# sbr.net
KiCad netlist of a schematic drawn in EAGLE
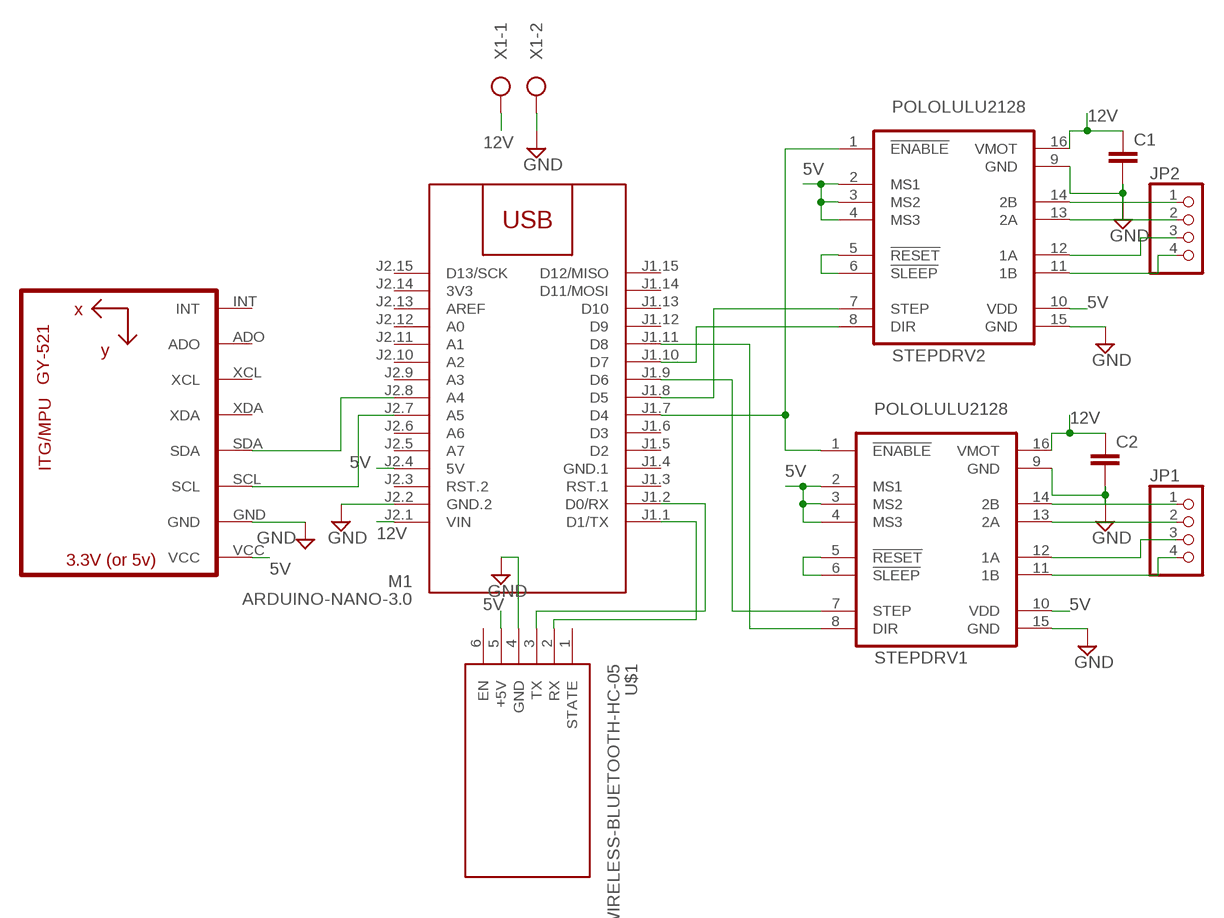
[diagram p0: schematic, sheet 1]

(export (version "E")
  (design (tool "Eeschema 10.0.6"))
  (components
    (comp (ref "C1")
      (value "C-EU025-024X044")
      (footprint "eagle-import:C025-024X044")
      (libsource (lib "eagle-import") (part "C-EU025-024X044"))
    )
    (comp (ref "C2")
      (value "C-EU025-024X044")
      (footprint "eagle-import:C025-024X044")
      (libsource (lib "eagle-import") (part "C-EU025-024X044"))
    )
    (comp (ref "JP1")
      (value "PINHD-1X4")
      (footprint "eagle-import:1X04")
      (libsource (lib "eagle-import") (part "PINHD-1X4"))
    )
    (comp (ref "JP2")
      (value "PINHD-1X4")
      (footprint "eagle-import:1X04")
      (libsource (lib "eagle-import") (part "PINHD-1X4"))
    )
    (comp (ref "M1")
      (value "ARDUINO-NANO-3.0")
      (footprint "eagle-import:ARDUINO-NANO-3.0")
      (libsource (lib "eagle-import") (part "ARDUINO-NANO-3.0"))
    )
    (comp (ref "STEPDRV1")
      (value "POLOLULU2128")
      (footprint "eagle-import:POLOLULU2128")
      (libsource (lib "eagle-import") (part "POLOLULU2128"))
    )
    (comp (ref "STEPDRV2")
      (value "POLOLULU2128")
      (footprint "eagle-import:POLOLULU2128")
      (libsource (lib "eagle-import") (part "POLOLULU2128"))
    )
    (comp (ref "U$1")
      (value "WIRELESS-BLUETOOTH-HC-05")
      (footprint "eagle-import:WIRELESS-BLUETOOTH-HC-05")
      (libsource (lib "eagle-import") (part "WIRELESS-BLUETOOTH-HC-05"))
    )
    (comp (ref "U1")
      (value "GY-521MPU6050")
      (footprint "eagle-import:GY-521")
      (libsource (lib "eagle-import") (part "GY-521MPU6050"))
    )
    (comp (ref "X1")
      (value "W237-102")
      (footprint "eagle-import:W237-102")
      (fields (field (name "MPN") "237-102"))
      (libsource (lib "eagle-import") (part "W237-102"))
    )
  )
  (nets
    (net (code "1") (name "/3V3") (class "Default")
      (node (ref "M1") (pin "J2.14") (pinfunction "3V3_J2.14") (pintype "power_in"))
    )
    (net (code "2") (name "/5V") (class "Default")
      (node (ref "M1") (pin "J2.4") (pinfunction "5V_J2.4") (pintype "power_in"))
      (node (ref "STEPDRV1") (pin "10") (pinfunction "VDD_10") (pintype "power_in"))
      (node (ref "STEPDRV1") (pin "2") (pinfunction "MS1_2") (pintype "input"))
      (node (ref "STEPDRV1") (pin "3") (pinfunction "MS2_3") (pintype "input"))
      (node (ref "STEPDRV1") (pin "4") (pinfunction "MS3_4") (pintype "input"))
      (node (ref "STEPDRV2") (pin "10") (pinfunction "VDD_10") (pintype "power_in"))
      (node (ref "STEPDRV2") (pin "2") (pinfunction "MS1_2") (pintype "input"))
      (node (ref "STEPDRV2") (pin "3") (pinfunction "MS2_3") (pintype "input"))
      (node (ref "STEPDRV2") (pin "4") (pinfunction "MS3_4") (pintype "input"))
      (node (ref "U$1") (pin "5") (pinfunction "+5V_5") (pintype "power_in"))
      (node (ref "U1") (pin "VCC") (pinfunction "VCC_VCC") (pintype "bidirectional"))
    )
    (net (code "3") (name "/12V") (class "Default")
      (node (ref "C1") (pin "1") (pinfunction "1_1") (pintype "passive"))
      (node (ref "C2") (pin "1") (pinfunction "1_1") (pintype "passive"))
      (node (ref "M1") (pin "J2.1") (pinfunction "VIN_J2.1") (pintype "power_in"))
      (node (ref "STEPDRV1") (pin "16") (pinfunction "VMOT_16") (pintype "power_in"))
      (node (ref "STEPDRV2") (pin "16") (pinfunction "VMOT_16") (pintype "power_in"))
      (node (ref "X1") (pin "1") (pinfunction "KL_1") (pintype "passive"))
    )
    (net (code "4") (name "/GND.1") (class "Default")
      (node (ref "M1") (pin "J1.4") (pinfunction "GND.1_J1.4") (pintype "power_in"))
    )
    (net (code "5") (name "GND") (class "Default")
      (node (ref "C1") (pin "2") (pinfunction "2_2") (pintype "passive"))
      (node (ref "C2") (pin "2") (pinfunction "2_2") (pintype "passive"))
      (node (ref "M1") (pin "J2.2") (pinfunction "GND.2_J2.2") (pintype "power_in"))
      (node (ref "STEPDRV1") (pin "15") (pinfunction "GND_15") (pintype "power_in"))
      (node (ref "STEPDRV1") (pin "9") (pinfunction "GND_9") (pintype "power_in"))
      (node (ref "STEPDRV2") (pin "15") (pinfunction "GND_15") (pintype "power_in"))
      (node (ref "STEPDRV2") (pin "9") (pinfunction "GND_9") (pintype "power_in"))
      (node (ref "U$1") (pin "4") (pinfunction "GND_4") (pintype "power_in"))
      (node (ref "U1") (pin "GND") (pinfunction "GND_GND") (pintype "bidirectional"))
      (node (ref "X1") (pin "2") (pinfunction "KL_2") (pintype "passive"))
    )
    (net (code "6") (name "Net-(M1-A4)") (class "Default")
      (node (ref "M1") (pin "J2.8") (pinfunction "A4_J2.8") (pintype "bidirectional"))
      (node (ref "U1") (pin "SDA") (pinfunction "SDA_SDA") (pintype "bidirectional"))
    )
    (net (code "7") (name "Net-(M1-A5)") (class "Default")
      (node (ref "M1") (pin "J2.7") (pinfunction "A5_J2.7") (pintype "bidirectional"))
      (node (ref "U1") (pin "SCL") (pinfunction "SCL_SCL") (pintype "bidirectional"))
    )
    (net (code "8") (name "Net-(M1-D0{slash}RX)") (class "Default")
      (node (ref "M1") (pin "J1.2") (pinfunction "D0/RX_J1.2") (pintype "bidirectional"))
      (node (ref "U$1") (pin "3") (pinfunction "TX_3") (pintype "bidirectional"))
    )
    (net (code "9") (name "Net-(M1-D1{slash}TX)") (class "Default")
      (node (ref "M1") (pin "J1.1") (pinfunction "D1/TX_J1.1") (pintype "bidirectional"))
      (node (ref "U$1") (pin "2") (pinfunction "RX_2") (pintype "bidirectional"))
    )
    (net (code "10") (name "Net-(M1-D4)") (class "Default")
      (node (ref "M1") (pin "J1.7") (pinfunction "D4_J1.7") (pintype "bidirectional"))
      (node (ref "STEPDRV1") (pin "1") (pinfunction "~{ENABLE}_1") (pintype "input"))
      (node (ref "STEPDRV2") (pin "1") (pinfunction "~{ENABLE}_1") (pintype "input"))
    )
    (net (code "11") (name "Net-(M1-D5)") (class "Default")
      (node (ref "M1") (pin "J1.8") (pinfunction "D5_J1.8") (pintype "bidirectional"))
      (node (ref "STEPDRV2") (pin "7") (pinfunction "STEP_7") (pintype "input"))
    )
    (net (code "12") (name "Net-(M1-D6)") (class "Default")
      (node (ref "M1") (pin "J1.9") (pinfunction "D6_J1.9") (pintype "bidirectional"))
      (node (ref "STEPDRV1") (pin "7") (pinfunction "STEP_7") (pintype "input"))
    )
    (net (code "13") (name "Net-(M1-D7)") (class "Default")
      (node (ref "M1") (pin "J1.10") (pinfunction "D7_J1.10") (pintype "bidirectional"))
      (node (ref "STEPDRV2") (pin "8") (pinfunction "DIR_8") (pintype "input"))
    )
    (net (code "14") (name "Net-(M1-D8)") (class "Default")
      (node (ref "M1") (pin "J1.11") (pinfunction "D8_J1.11") (pintype "bidirectional"))
      (node (ref "STEPDRV1") (pin "8") (pinfunction "DIR_8") (pintype "input"))
    )
    (net (code "15") (name "Net-(STEPDRV1-1A)") (class "Default")
      (node (ref "JP1") (pin "3") (pinfunction "3_3") (pintype "passive"))
      (node (ref "STEPDRV1") (pin "12") (pinfunction "1A_12") (pintype "output"))
    )
    (net (code "16") (name "Net-(STEPDRV1-1B)") (class "Default")
      (node (ref "JP1") (pin "4") (pinfunction "4_4") (pintype "passive"))
      (node (ref "STEPDRV1") (pin "11") (pinfunction "1B_11") (pintype "output"))
    )
    (net (code "17") (name "Net-(STEPDRV1-2A)") (class "Default")
      (node (ref "JP1") (pin "2") (pinfunction "2_2") (pintype "passive"))
      (node (ref "STEPDRV1") (pin "13") (pinfunction "2A_13") (pintype "output"))
    )
    (net (code "18") (name "Net-(STEPDRV1-2B)") (class "Default")
      (node (ref "JP1") (pin "1") (pinfunction "1_1") (pintype "passive"))
      (node (ref "STEPDRV1") (pin "14") (pinfunction "2B_14") (pintype "output"))
    )
    (net (code "19") (name "Net-(STEPDRV1-~{RESET})") (class "Default")
      (node (ref "STEPDRV1") (pin "5") (pinfunction "~{RESET}_5") (pintype "input"))
      (node (ref "STEPDRV1") (pin "6") (pinfunction "~{SLEEP}_6") (pintype "input"))
    )
    (net (code "20") (name "Net-(STEPDRV2-1A)") (class "Default")
      (node (ref "JP2") (pin "3") (pinfunction "3_3") (pintype "passive"))
      (node (ref "STEPDRV2") (pin "12") (pinfunction "1A_12") (pintype "output"))
    )
    (net (code "21") (name "Net-(STEPDRV2-1B)") (class "Default")
      (node (ref "JP2") (pin "4") (pinfunction "4_4") (pintype "passive"))
      (node (ref "STEPDRV2") (pin "11") (pinfunction "1B_11") (pintype "output"))
    )
    (net (code "22") (name "Net-(STEPDRV2-2A)") (class "Default")
      (node (ref "JP2") (pin "2") (pinfunction "2_2") (pintype "passive"))
      (node (ref "STEPDRV2") (pin "13") (pinfunction "2A_13") (pintype "output"))
    )
    (net (code "23") (name "Net-(STEPDRV2-2B)") (class "Default")
      (node (ref "JP2") (pin "1") (pinfunction "1_1") (pintype "passive"))
      (node (ref "STEPDRV2") (pin "14") (pinfunction "2B_14") (pintype "output"))
    )
    (net (code "24") (name "Net-(STEPDRV2-~{RESET})") (class "Default")
      (node (ref "STEPDRV2") (pin "5") (pinfunction "~{RESET}_5") (pintype "input"))
      (node (ref "STEPDRV2") (pin "6") (pinfunction "~{SLEEP}_6") (pintype "input"))
    )
    (net (code "25") (name "unconnected-(M1-A0-PadJ2.12)") (class "Default")
      (node (ref "M1") (pin "J2.12") (pinfunction "A0_J2.12") (pintype "bidirectional"))
    )
    (net (code "26") (name "unconnected-(M1-A1-PadJ2.11)") (class "Default")
      (node (ref "M1") (pin "J2.11") (pinfunction "A1_J2.11") (pintype "bidirectional"))
    )
    (net (code "27") (name "unconnected-(M1-A2-PadJ2.10)") (class "Default")
      (node (ref "M1") (pin "J2.10") (pinfunction "A2_J2.10") (pintype "bidirectional"))
    )
    (net (code "28") (name "unconnected-(M1-A3-PadJ2.9)") (class "Default")
      (node (ref "M1") (pin "J2.9") (pinfunction "A3_J2.9") (pintype "bidirectional"))
    )
    (net (code "29") (name "unconnected-(M1-A6-PadJ2.6)") (class "Default")
      (node (ref "M1") (pin "J2.6") (pinfunction "A6_J2.6") (pintype "bidirectional"))
    )
    (net (code "30") (name "unconnected-(M1-A7-PadJ2.5)") (class "Default")
      (node (ref "M1") (pin "J2.5") (pinfunction "A7_J2.5") (pintype "bidirectional"))
    )
    (net (code "31") (name "unconnected-(M1-AREF-PadJ2.13)") (class "Default")
      (node (ref "M1") (pin "J2.13") (pinfunction "AREF_J2.13") (pintype "bidirectional"))
    )
    (net (code "32") (name "unconnected-(M1-D2-PadJ1.5)") (class "Default")
      (node (ref "M1") (pin "J1.5") (pinfunction "D2_J1.5") (pintype "bidirectional"))
    )
    (net (code "33") (name "unconnected-(M1-D3-PadJ1.6)") (class "Default")
      (node (ref "M1") (pin "J1.6") (pinfunction "D3_J1.6") (pintype "bidirectional"))
    )
    (net (code "34") (name "unconnected-(M1-D9-PadJ1.12)") (class "Default")
      (node (ref "M1") (pin "J1.12") (pinfunction "D9_J1.12") (pintype "bidirectional"))
    )
    (net (code "35") (name "unconnected-(M1-D10-PadJ1.13)") (class "Default")
      (node (ref "M1") (pin "J1.13") (pinfunction "D10_J1.13") (pintype "bidirectional"))
    )
    (net (code "36") (name "unconnected-(M1-D11{slash}MOSI-PadJ1.14)") (class "Default")
      (node (ref "M1") (pin "J1.14") (pinfunction "D11/MOSI_J1.14") (pintype "bidirectional"))
    )
    (net (code "37") (name "unconnected-(M1-D12{slash}MISO-PadJ1.15)") (class "Default")
      (node (ref "M1") (pin "J1.15") (pinfunction "D12/MISO_J1.15") (pintype "bidirectional"))
    )
    (net (code "38") (name "unconnected-(M1-D13{slash}SCK-PadJ2.15)") (class "Default")
      (node (ref "M1") (pin "J2.15") (pinfunction "D13/SCK_J2.15") (pintype "bidirectional"))
    )
    (net (code "39") (name "unconnected-(M1-RST.1-PadJ1.3)") (class "Default")
      (node (ref "M1") (pin "J1.3") (pinfunction "RST.1_J1.3") (pintype "bidirectional"))
    )
    (net (code "40") (name "unconnected-(M1-RST.2-PadJ2.3)") (class "Default")
      (node (ref "M1") (pin "J2.3") (pinfunction "RST.2_J2.3") (pintype "bidirectional"))
    )
    (net (code "41") (name "unconnected-(U$1-EN-Pad6)") (class "Default")
      (node (ref "U$1") (pin "6") (pinfunction "EN_6") (pintype "bidirectional"))
    )
    (net (code "42") (name "unconnected-(U$1-STATE-Pad1)") (class "Default")
      (node (ref "U$1") (pin "1") (pinfunction "STATE_1") (pintype "bidirectional"))
    )
    (net (code "43") (name "unconnected-(U1-PadADO)") (class "Default")
      (node (ref "U1") (pin "ADO") (pinfunction "ADO_ADO") (pintype "bidirectional"))
    )
    (net (code "44") (name "unconnected-(U1-PadINT)") (class "Default")
      (node (ref "U1") (pin "INT") (pinfunction "INT_INT") (pintype "bidirectional"))
    )
    (net (code "45") (name "unconnected-(U1-PadXCL)") (class "Default")
      (node (ref "U1") (pin "XCL") (pinfunction "XCL_XCL") (pintype "bidirectional"))
    )
    (net (code "46") (name "unconnected-(U1-PadXDA)") (class "Default")
      (node (ref "U1") (pin "XDA") (pinfunction "XDA_XDA") (pintype "bidirectional"))
    )
  )
)
